# usb_hub.net
KiCad netlist of a schematic drawn in Altium Designer
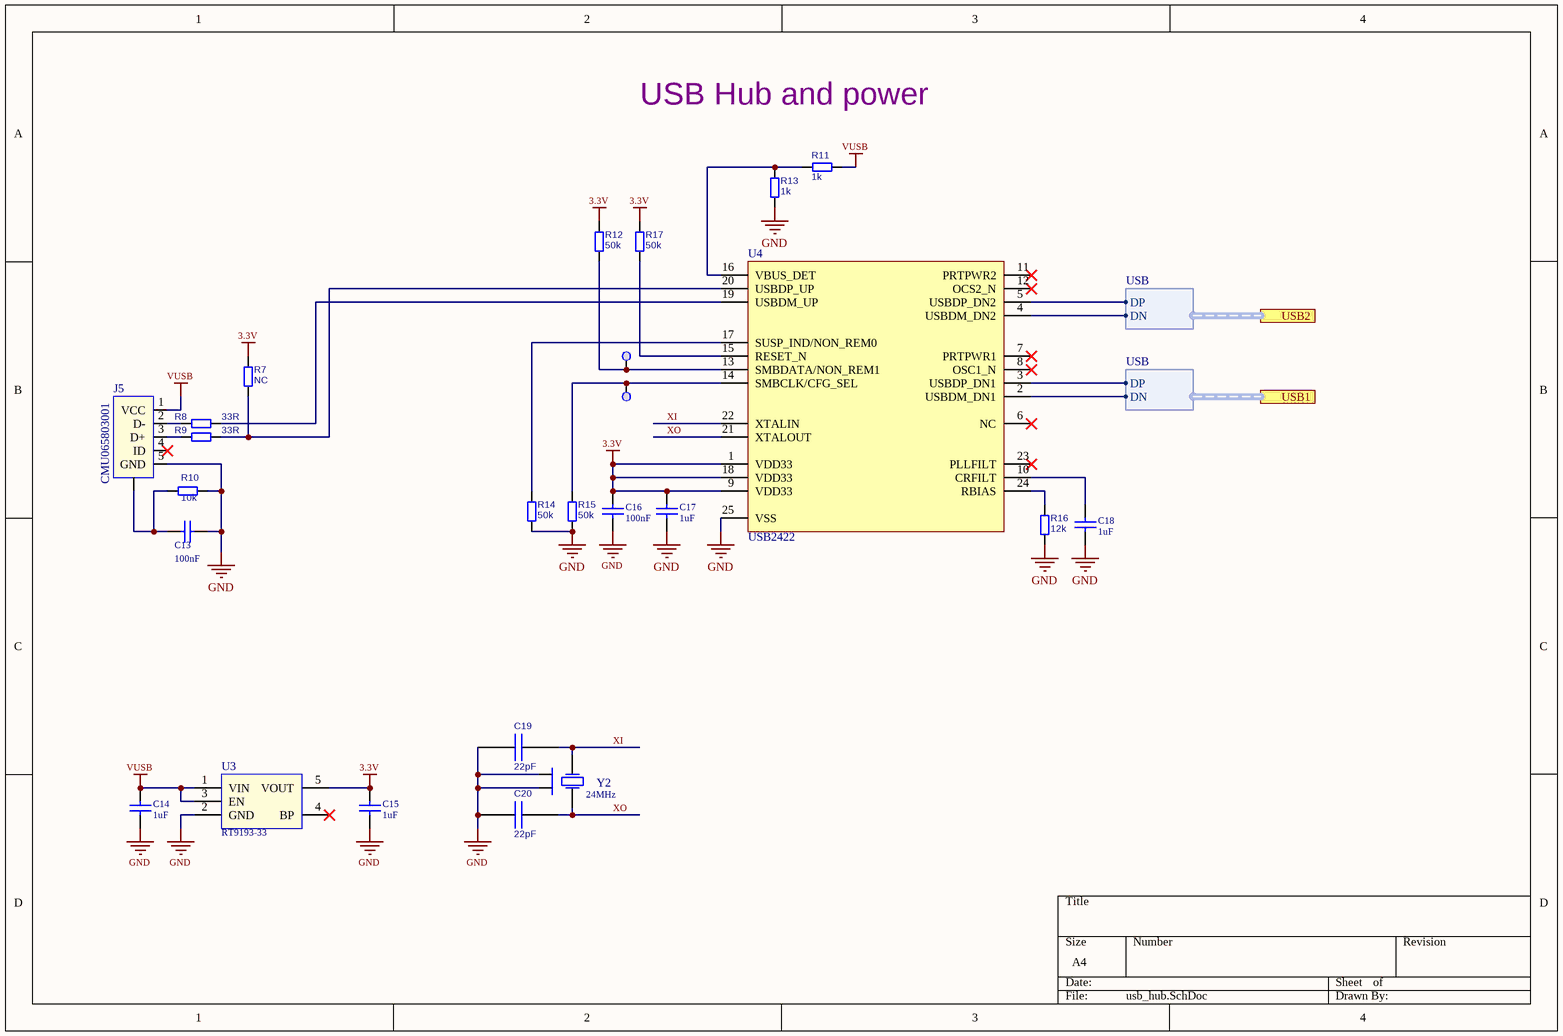
[diagram p0: usb_hub.SchDoc]

(export (version "E")
  (design (tool "Eeschema 10.0.6"))
  (components
    (comp (ref "C13")
      (value "100nF")
      (footprint "C0402")
      (description "Capacitor")
      (fields (field (name "PUBLISHER") "Altium Limited"))
      (libsource (lib "Miscellaneous Devices") (part "Cap"))
    )
    (comp (ref "C14")
      (value "1uF")
      (footprint "C0603")
      (description "Capacitor")
      (fields (field (name "PUBLISHER") "Altium Limited"))
      (libsource (lib "Miscellaneous Devices") (part "Cap"))
    )
    (comp (ref "C15")
      (value "1uF")
      (footprint "C0603")
      (description "Capacitor")
      (fields (field (name "PUBLISHER") "Altium Limited"))
      (libsource (lib "Miscellaneous Devices") (part "Cap"))
    )
    (comp (ref "C16")
      (value "100nF")
      (footprint "C0402")
      (description "Capacitor")
      (fields (field (name "PUBLISHER") "Altium Limited"))
      (libsource (lib "Miscellaneous Devices") (part "Cap"))
    )
    (comp (ref "C17")
      (value "1uF")
      (footprint "C0603")
      (description "Capacitor")
      (fields (field (name "PUBLISHER") "Altium Limited"))
      (libsource (lib "Miscellaneous Devices") (part "Cap"))
    )
    (comp (ref "C18")
      (value "1uF")
      (footprint "C0603")
      (description "Capacitor")
      (fields (field (name "PUBLISHER") "Altium Limited"))
      (libsource (lib "Miscellaneous Devices") (part "Cap"))
    )
    (comp (ref "C19")
      (value "22pF")
      (footprint "C0402")
      (description "Ceramic Capacitor")
      (libsource (lib "hdesign") (part "Cap1"))
    )
    (comp (ref "C20")
      (value "22pF")
      (footprint "C0402")
      (description "Ceramic Capacitor")
      (libsource (lib "hdesign") (part "Cap1"))
    )
    (comp (ref "J5")
      (value "CMU065803001")
      (footprint "CMU065803001")
      (description "MICRO USB 5P FEMALE DIP B -TYPE")
      (fields (field (name "MANUFACTURER") "CSCONN"))
      (libsource (lib "hdesign") (part "CMU065803001"))
    )
    (comp (ref "R7")
      (value "NC")
      (footprint "R0402")
      (description "Resistor")
      (libsource (lib "hdesign") (part "Res"))
    )
    (comp (ref "R8")
      (value "33R")
      (footprint "R0402")
      (description "Resistor")
      (libsource (lib "hdesign") (part "Res"))
    )
    (comp (ref "R9")
      (value "33R")
      (footprint "R0402")
      (description "Resistor")
      (libsource (lib "hdesign") (part "Res"))
    )
    (comp (ref "R10")
      (value "10k")
      (footprint "R0402")
      (description "Resistor")
      (libsource (lib "hdesign") (part "Res"))
    )
    (comp (ref "R11")
      (value "1k")
      (footprint "R0402")
      (description "Resistor")
      (libsource (lib "hdesign") (part "Res"))
    )
    (comp (ref "R12")
      (value "50k")
      (footprint "R0402")
      (description "Resistor")
      (libsource (lib "hdesign") (part "Res"))
    )
    (comp (ref "R13")
      (value "1k")
      (footprint "R0402")
      (description "Resistor")
      (libsource (lib "hdesign") (part "Res"))
    )
    (comp (ref "R14")
      (value "50k")
      (footprint "R0402")
      (description "Resistor")
      (libsource (lib "hdesign") (part "Res"))
    )
    (comp (ref "R15")
      (value "50k")
      (footprint "R0402")
      (description "Resistor")
      (libsource (lib "hdesign") (part "Res"))
    )
    (comp (ref "R16")
      (value "12k")
      (footprint "R0402")
      (description "Resistor")
      (libsource (lib "hdesign") (part "Res"))
    )
    (comp (ref "R17")
      (value "50k")
      (footprint "R0402")
      (description "Resistor")
      (libsource (lib "hdesign") (part "Res"))
    )
    (comp (ref "TP5")
      (value "TestPoint")
      (footprint "PAD1_07")
      (description "Test point")
      (libsource (lib "hdesign") (part "TestPoint"))
    )
    (comp (ref "TP6")
      (value "TestPoint")
      (footprint "PAD1_07")
      (description "Test point")
      (libsource (lib "hdesign") (part "TestPoint"))
    )
    (comp (ref "U3")
      (value "RT9193-33")
      (footprint "SOT23-5")
      (description "300mA, Ultra-Low Noise, Ultra-Fast CMOS LDO Regulator")
      (fields (field (name "MANUFACTURER") "RICHTEK"))
      (libsource (lib "hdesign") (part "RT9193"))
    )
    (comp (ref "U4")
      (value "USB2422")
      (footprint "QFN-24_4040")
      (description "USB 2.0 Hi-Speed 2-port Hub Controller")
      (fields (field (name "MANUFACTURER") "Microchip"))
      (libsource (lib "hdesign") (part "USB2422"))
    )
    (comp (ref "Y2")
      (value "24MHz")
      (footprint "XTAL_3225")
      (description "24Mhz CERAMIC SMD CRYSTAL")
      (libsource (lib "hdesign") (part "XTAL_4_PIN"))
    )
  )
  (nets
    (net (code "2") (name "/XI") (class "Default")
      (node (ref "C19") (pin "2") (pinfunction "N_2") (pintype "passive"))
      (node (ref "U4") (pin "22") (pinfunction "XTALIN_22") (pintype "passive"))
      (node (ref "Y2") (pin "1") (pinfunction "X1_1") (pintype "passive"))
    )
    (net (code "3") (name "/XO") (class "Default")
      (node (ref "C20") (pin "2") (pinfunction "N_2") (pintype "passive"))
      (node (ref "U4") (pin "21") (pinfunction "XTALOUT_21") (pintype "passive"))
      (node (ref "Y2") (pin "3") (pinfunction "X2_3") (pintype "passive"))
    )
    (net (code "5") (name "3.3V") (class "Default")
      (node (ref "C15") (pin "2") (pinfunction "2_2") (pintype "passive"))
      (node (ref "C16") (pin "2") (pinfunction "2_2") (pintype "passive"))
      (node (ref "C17") (pin "2") (pinfunction "2_2") (pintype "passive"))
      (node (ref "R12") (pin "2") (pinfunction "A_2") (pintype "passive"))
      (node (ref "R17") (pin "2") (pinfunction "A_2") (pintype "passive"))
      (node (ref "R7") (pin "1") (pinfunction "K_1") (pintype "passive"))
      (node (ref "U3") (pin "5") (pinfunction "VOUT_5") (pintype "passive"))
      (node (ref "U4") (pin "1") (pinfunction "VDD33_1") (pintype "passive"))
      (node (ref "U4") (pin "18") (pinfunction "VDD33_18") (pintype "passive"))
      (node (ref "U4") (pin "9") (pinfunction "VDD33_9") (pintype "passive"))
    )
    (net (code "6") (name "GND") (class "Default")
      (node (ref "C13") (pin "2") (pinfunction "2_2") (pintype "passive"))
      (node (ref "C14") (pin "1") (pinfunction "1_1") (pintype "passive"))
      (node (ref "C15") (pin "1") (pinfunction "1_1") (pintype "passive"))
      (node (ref "C16") (pin "1") (pinfunction "1_1") (pintype "passive"))
      (node (ref "C17") (pin "1") (pinfunction "1_1") (pintype "passive"))
      (node (ref "C18") (pin "1") (pinfunction "1_1") (pintype "passive"))
      (node (ref "C19") (pin "1") (pinfunction "P_1") (pintype "passive"))
      (node (ref "C20") (pin "1") (pinfunction "P_1") (pintype "passive"))
      (node (ref "J5") (pin "5") (pinfunction "GND_5") (pintype "passive"))
      (node (ref "R10") (pin "1") (pinfunction "K_1") (pintype "passive"))
      (node (ref "R13") (pin "1") (pinfunction "K_1") (pintype "passive"))
      (node (ref "R14") (pin "1") (pinfunction "K_1") (pintype "passive"))
      (node (ref "R15") (pin "1") (pinfunction "K_1") (pintype "passive"))
      (node (ref "R16") (pin "1") (pinfunction "K_1") (pintype "passive"))
      (node (ref "U3") (pin "2") (pinfunction "GND_2") (pintype "passive"))
      (node (ref "U4") (pin "25") (pinfunction "VSS_25") (pintype "passive"))
      (node (ref "Y2") (pin "2") (pinfunction "2_2") (pintype "passive"))
      (node (ref "Y2") (pin "4") (pinfunction "X2_4") (pintype "passive"))
    )
    (net (code "7") (name "Net-(J5-D+)") (class "Default")
      (node (ref "J5") (pin "3") (pinfunction "D+_3") (pintype "passive"))
      (node (ref "R9") (pin "2") (pinfunction "A_2") (pintype "passive"))
    )
    (net (code "8") (name "Net-(J5-D-)") (class "Default")
      (node (ref "J5") (pin "2") (pinfunction "D-_2") (pintype "passive"))
      (node (ref "R8") (pin "2") (pinfunction "A_2") (pintype "passive"))
    )
    (net (code "9") (name "Net-(R7-A)") (class "Default")
      (node (ref "R7") (pin "2") (pinfunction "A_2") (pintype "passive"))
      (node (ref "R9") (pin "1") (pinfunction "K_1") (pintype "passive"))
      (node (ref "U4") (pin "20") (pinfunction "USBDP_UP_20") (pintype "passive"))
    )
    (net (code "10") (name "Net-(R8-K)") (class "Default")
      (node (ref "R8") (pin "1") (pinfunction "K_1") (pintype "passive"))
      (node (ref "U4") (pin "19") (pinfunction "USBDM_UP_19") (pintype "passive"))
    )
    (net (code "11") (name "Net-(R10-A)") (class "Default")
      (node (ref "C13") (pin "1") (pinfunction "1_1") (pintype "passive"))
      (node (ref "J5") (pin "0") (pinfunction "0_0") (pintype "passive"))
      (node (ref "R10") (pin "2") (pinfunction "A_2") (pintype "passive"))
    )
    (net (code "12") (name "Net-(R11-A)") (class "Default")
      (node (ref "R11") (pin "2") (pinfunction "A_2") (pintype "passive"))
      (node (ref "R13") (pin "2") (pinfunction "A_2") (pintype "passive"))
      (node (ref "U4") (pin "16") (pinfunction "VBUS_DET_16") (pintype "passive"))
    )
    (net (code "13") (name "Net-(R12-K)") (class "Default")
      (node (ref "R12") (pin "1") (pinfunction "K_1") (pintype "passive"))
      (node (ref "TP5") (pin "1") (pinfunction "1_1") (pintype "passive"))
      (node (ref "U4") (pin "13") (pinfunction "SMBDATA/NON_REM1_13") (pintype "passive"))
    )
    (net (code "14") (name "Net-(R14-A)") (class "Default")
      (node (ref "R14") (pin "2") (pinfunction "A_2") (pintype "passive"))
      (node (ref "U4") (pin "17") (pinfunction "SUSP_IND/NON_REM0_17") (pintype "passive"))
    )
    (net (code "15") (name "Net-(R15-A)") (class "Default")
      (node (ref "R15") (pin "2") (pinfunction "A_2") (pintype "passive"))
      (node (ref "TP6") (pin "1") (pinfunction "1_1") (pintype "passive"))
      (node (ref "U4") (pin "14") (pinfunction "SMBCLK/CFG_SEL_14") (pintype "passive"))
    )
    (net (code "16") (name "Net-(R16-A)") (class "Default")
      (node (ref "R16") (pin "2") (pinfunction "A_2") (pintype "passive"))
      (node (ref "U4") (pin "24") (pinfunction "RBIAS_24") (pintype "passive"))
    )
    (net (code "17") (name "Net-(R17-K)") (class "Default")
      (node (ref "R17") (pin "1") (pinfunction "K_1") (pintype "passive"))
      (node (ref "U4") (pin "15") (pinfunction "RESET_N_15") (pintype "passive"))
    )
    (net (code "18") (name "Net-(U4-CRFILT)") (class "Default")
      (node (ref "C18") (pin "2") (pinfunction "2_2") (pintype "passive"))
      (node (ref "U4") (pin "10") (pinfunction "CRFILT_10") (pintype "passive"))
    )
    (net (code "19") (name "VUSB") (class "Default")
      (node (ref "C14") (pin "2") (pinfunction "2_2") (pintype "passive"))
      (node (ref "J5") (pin "1") (pinfunction "VCC_1") (pintype "passive"))
      (node (ref "R11") (pin "1") (pinfunction "K_1") (pintype "passive"))
      (node (ref "U3") (pin "1") (pinfunction "VIN_1") (pintype "passive"))
      (node (ref "U3") (pin "3") (pinfunction "EN_3") (pintype "passive"))
    )
    (net (code "20") (name "unconnected-(J5-ID-Pad4)") (class "Default")
      (node (ref "J5") (pin "4") (pinfunction "ID_4") (pintype "passive+no_connect"))
    )
    (net (code "21") (name "unconnected-(U3-BP-Pad4)") (class "Default")
      (node (ref "U3") (pin "4") (pinfunction "BP_4") (pintype "passive+no_connect"))
    )
    (net (code "22") (name "unconnected-(U4-NC-Pad6)") (class "Default")
      (node (ref "U4") (pin "6") (pinfunction "NC_6") (pintype "passive+no_connect"))
    )
    (net (code "23") (name "unconnected-(U4-OCS2_N-Pad12)") (class "Default")
      (node (ref "U4") (pin "12") (pinfunction "OCS2_N_12") (pintype "passive+no_connect"))
    )
    (net (code "24") (name "unconnected-(U4-OSC1_N-Pad8)") (class "Default")
      (node (ref "U4") (pin "8") (pinfunction "OSC1_N_8") (pintype "passive+no_connect"))
    )
    (net (code "25") (name "unconnected-(U4-PLLFILT-Pad23)") (class "Default")
      (node (ref "U4") (pin "23") (pinfunction "PLLFILT_23") (pintype "passive+no_connect"))
    )
    (net (code "26") (name "unconnected-(U4-PRTPWR1-Pad7)") (class "Default")
      (node (ref "U4") (pin "7") (pinfunction "PRTPWR1_7") (pintype "passive+no_connect"))
    )
    (net (code "27") (name "unconnected-(U4-PRTPWR2-Pad11)") (class "Default")
      (node (ref "U4") (pin "11") (pinfunction "PRTPWR2_11") (pintype "passive+no_connect"))
    )
    (net (code "28") (name "unconnected-(U4-USBDM_DN1-Pad2)") (class "Default")
      (node (ref "U4") (pin "2") (pinfunction "USBDM_DN1_2") (pintype "passive"))
    )
    (net (code "29") (name "unconnected-(U4-USBDM_DN2-Pad4)") (class "Default")
      (node (ref "U4") (pin "4") (pinfunction "USBDM_DN2_4") (pintype "passive"))
    )
    (net (code "30") (name "unconnected-(U4-USBDP_DN1-Pad3)") (class "Default")
      (node (ref "U4") (pin "3") (pinfunction "USBDP_DN1_3") (pintype "passive"))
    )
    (net (code "31") (name "unconnected-(U4-USBDP_DN2-Pad5)") (class "Default")
      (node (ref "U4") (pin "5") (pinfunction "USBDP_DN2_5") (pintype "passive"))
    )
  )
)
